# uvc_air_filter_psu.net
KiCad netlist of a schematic drawn in EAGLE
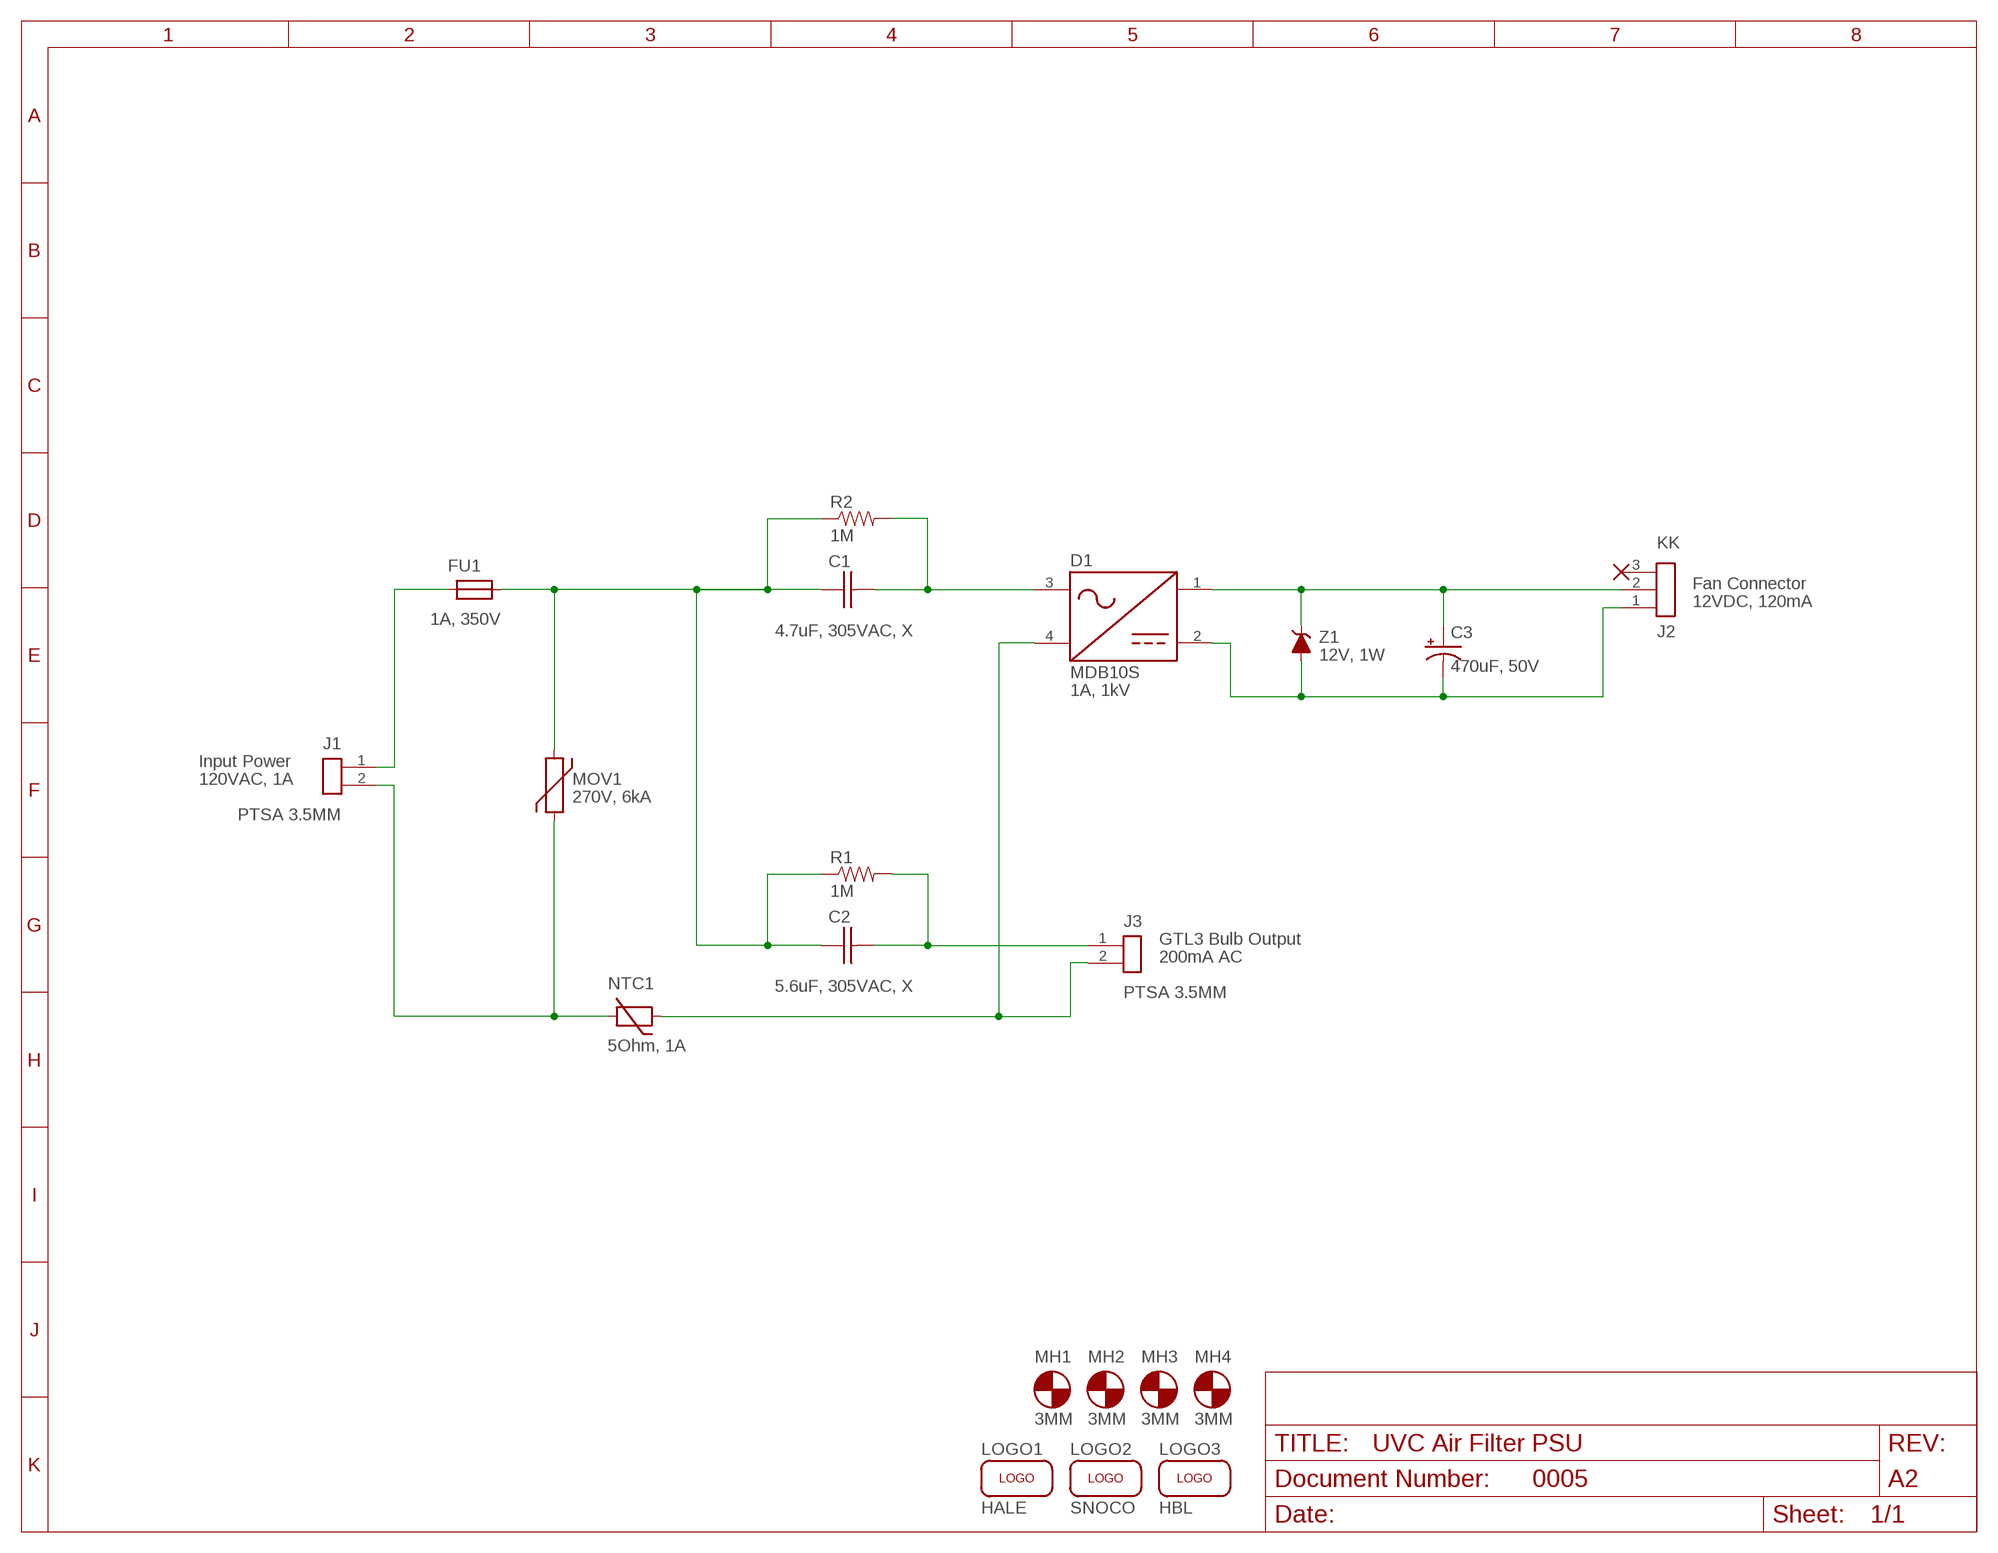
[diagram p0: schematic, sheet 1]

(export (version "E")
  (design (tool "Eeschema 10.0.6"))
  (components
    (comp (ref "C1")
      (value "4.7uF, 305VAC, X")
      (footprint "eagle-import:CAP-27.5MM")
      (fields (field (name "MFG") "TDK Electronics Inc."))
      (libsource (lib "eagle-import") (part "C-27.5MM-4.7UF/305VAC"))
    )
    (comp (ref "C2")
      (value "5.6uF, 305VAC, X")
      (footprint "eagle-import:CAP-27.5MM")
      (fields (field (name "MFG") "TDK Electronics Inc."))
      (libsource (lib "eagle-import") (part "C-27.5MM-5.6UF/305VAC"))
    )
    (comp (ref "C3")
      (value "470uF, 50V")
      (footprint "eagle-import:CAP-5MM-10MM")
      (fields
        (field (name "MFG") "Panasonic Electronic Components")
        (field (name "DIGIKEY") "P5185-ND")
        (field (name "PN") "ECA-1HM471")
      )
      (libsource (lib "eagle-import") (part "C-POL-10MM-470UF/50V"))
    )
    (comp (ref "D1")
      (value "1A, 1kV")
      (footprint "eagle-import:TSSOP-4")
      (fields (field (name "MFG") "ON Semiconductor"))
      (libsource (lib "eagle-import") (part "RECTIFIER-MDB-MDB10S"))
    )
    (comp (ref "FU1")
      (value "1A, 350V")
      (footprint "eagle-import:FUSE-5X15MM")
      (fields (field (name "MFG") "Littelfuse Inc."))
      (libsource (lib "eagle-import") (part "FUSE-TH-5X15MM-1A"))
    )
    (comp (ref "J1")
      (value "PTSA 3.5MM")
      (footprint "eagle-import:HEADER-PTSA-3.5MM-1X2")
      (fields (field (name "MFG") "Phoenix Contact"))
      (libsource (lib "eagle-import") (part "HEADER-1X2-PTSA-3.5MM"))
    )
    (comp (ref "J2")
      (value "KK")
      (footprint "eagle-import:HEADER-KK-1X3")
      (fields (field (name "MFG") "Molex"))
      (libsource (lib "eagle-import") (part "HEADER-1X3-KK"))
    )
    (comp (ref "J3")
      (value "PTSA 3.5MM")
      (footprint "eagle-import:HEADER-PTSA-3.5MM-1X2")
      (fields (field (name "MFG") "Phoenix Contact"))
      (libsource (lib "eagle-import") (part "HEADER-1X2-PTSA-3.5MM"))
    )
    (comp (ref "LOGO1")
      (value "HALE")
      (footprint "eagle-import:HALE-SILK-ICON")
      (libsource (lib "eagle-import") (part "LOGO-HALE"))
    )
    (comp (ref "LOGO2")
      (value "SNOCO")
      (footprint "eagle-import:SNOCO-SILK-ICON")
      (libsource (lib "eagle-import") (part "LOGO-SNOCO"))
    )
    (comp (ref "LOGO3")
      (value "HBL")
      (footprint "eagle-import:HACKERBOT-SILK-ICON")
      (libsource (lib "eagle-import") (part "LOGO-HACKERBOT"))
    )
    (comp (ref "MH1")
      (value "3MM")
      (footprint "eagle-import:MH-M3")
      (libsource (lib "eagle-import") (part "MH-M3"))
    )
    (comp (ref "MH2")
      (value "3MM")
      (footprint "eagle-import:MH-M3")
      (libsource (lib "eagle-import") (part "MH-M3"))
    )
    (comp (ref "MH3")
      (value "3MM")
      (footprint "eagle-import:MH-M3")
      (libsource (lib "eagle-import") (part "MH-M3"))
    )
    (comp (ref "MH4")
      (value "3MM")
      (footprint "eagle-import:MH-M3")
      (libsource (lib "eagle-import") (part "MH-M3"))
    )
    (comp (ref "MOV1")
      (value "270V, 6kA")
      (footprint "eagle-import:MOV-B722-7.5MM")
      (fields (field (name "MFG") "TDK Electronics Inc."))
      (libsource (lib "eagle-import") (part "MOV-B722-7.5MM-270V/6KA"))
    )
    (comp (ref "NTC1")
      (value "5Ohm, 1A")
      (footprint "eagle-import:MF72-D5-NTC")
      (fields (field (name "MFG") "Ametherm"))
      (libsource (lib "eagle-import") (part "NTC-5MM-TH-5OHM/1A"))
    )
    (comp (ref "R1")
      (value "1M")
      (footprint "eagle-import:1206-NONPOLAR")
      (fields
        (field (name "MFG") "Yageo")
        (field (name "DIGIKEY") "311-1.00MFRCT-ND")
        (field (name "PN") "RC1206FR-071ML")
      )
      (libsource (lib "eagle-import") (part "R-1206-15"))
    )
    (comp (ref "R2")
      (value "1M")
      (footprint "eagle-import:1206-NONPOLAR")
      (fields
        (field (name "MFG") "Yageo")
        (field (name "DIGIKEY") "311-1.00MFRCT-ND")
        (field (name "PN") "RC1206FR-071ML")
      )
      (libsource (lib "eagle-import") (part "R-1206-15"))
    )
    (comp (ref "U$1")
      (value "FRAME-8.5X11-LANDSCAPE-LET")
      (footprint "eagle-import:FRAME-8.5X11-LANDSCAPE")
      (fields
        (field (name "DOCNUM") "0005")
        (field (name "REV") "A2")
        (field (name "TITLE") "UVC Air Filter PSU")
      )
      (libsource (lib "eagle-import") (part "FRAME-8.5X11-LANDSCAPE-LET"))
    )
    (comp (ref "Z1")
      (value "12V, 1W")
      (footprint "eagle-import:SMA")
      (fields (field (name "MFG") "Diodes Incorporated"))
      (libsource (lib "eagle-import") (part "ZENER-SMA-12V/1W"))
    )
  )
  (nets
    (net (code "1") (name "Net-(C1-+)") (class "Default")
      (node (ref "C1") (pin "1") (pinfunction "+_1") (pintype "passive"))
      (node (ref "C2") (pin "1") (pinfunction "+_1") (pintype "passive"))
      (node (ref "FU1") (pin "2") (pinfunction "2_2") (pintype "passive"))
      (node (ref "MOV1") (pin "1") (pinfunction "1_1") (pintype "passive"))
      (node (ref "R1") (pin "1") (pinfunction "1_1") (pintype "passive"))
      (node (ref "R2") (pin "1") (pinfunction "1_1") (pintype "passive"))
    )
    (net (code "2") (name "Net-(C1--)") (class "Default")
      (node (ref "C1") (pin "2") (pinfunction "-_2") (pintype "passive"))
      (node (ref "D1") (pin "3") (pinfunction "1_3") (pintype "power_in"))
      (node (ref "R2") (pin "2") (pinfunction "2_2") (pintype "passive"))
    )
    (net (code "3") (name "Net-(C2--)") (class "Default")
      (node (ref "C2") (pin "2") (pinfunction "-_2") (pintype "passive"))
      (node (ref "J3") (pin "1") (pinfunction "1_1") (pintype "passive"))
      (node (ref "R1") (pin "2") (pinfunction "2_2") (pintype "passive"))
    )
    (net (code "4") (name "Net-(C3-+)") (class "Default")
      (node (ref "C3") (pin "1") (pinfunction "+_1") (pintype "passive"))
      (node (ref "D1") (pin "1") (pinfunction "+_1") (pintype "power_in"))
      (node (ref "J2") (pin "2") (pinfunction "2_2") (pintype "passive"))
      (node (ref "Z1") (pin "2") (pinfunction "C_2") (pintype "passive"))
    )
    (net (code "5") (name "Net-(C3--)") (class "Default")
      (node (ref "C3") (pin "2") (pinfunction "-_2") (pintype "passive"))
      (node (ref "D1") (pin "2") (pinfunction "-_2") (pintype "power_in"))
      (node (ref "J2") (pin "1") (pinfunction "1_1") (pintype "passive"))
      (node (ref "Z1") (pin "1") (pinfunction "A_1") (pintype "passive"))
    )
    (net (code "6") (name "Net-(D1-2)") (class "Default")
      (node (ref "D1") (pin "4") (pinfunction "2_4") (pintype "power_in"))
      (node (ref "J3") (pin "2") (pinfunction "2_2") (pintype "passive"))
      (node (ref "NTC1") (pin "2") (pinfunction "2_2") (pintype "passive"))
    )
    (net (code "7") (name "Net-(FU1-Pad1)") (class "Default")
      (node (ref "FU1") (pin "1") (pinfunction "1_1") (pintype "passive"))
      (node (ref "J1") (pin "1") (pinfunction "1_1") (pintype "passive"))
    )
    (net (code "8") (name "Net-(J1-Pad2)") (class "Default")
      (node (ref "J1") (pin "2") (pinfunction "2_2") (pintype "passive"))
      (node (ref "MOV1") (pin "2") (pinfunction "2_2") (pintype "passive"))
      (node (ref "NTC1") (pin "1") (pinfunction "1_1") (pintype "passive"))
    )
    (net (code "9") (name "unconnected-(J2-Pad3)") (class "Default")
      (node (ref "J2") (pin "3") (pinfunction "3_3") (pintype "passive"))
    )
  )
)
